# Port.net
KiCad netlist of a schematic drawn in Altium Designer
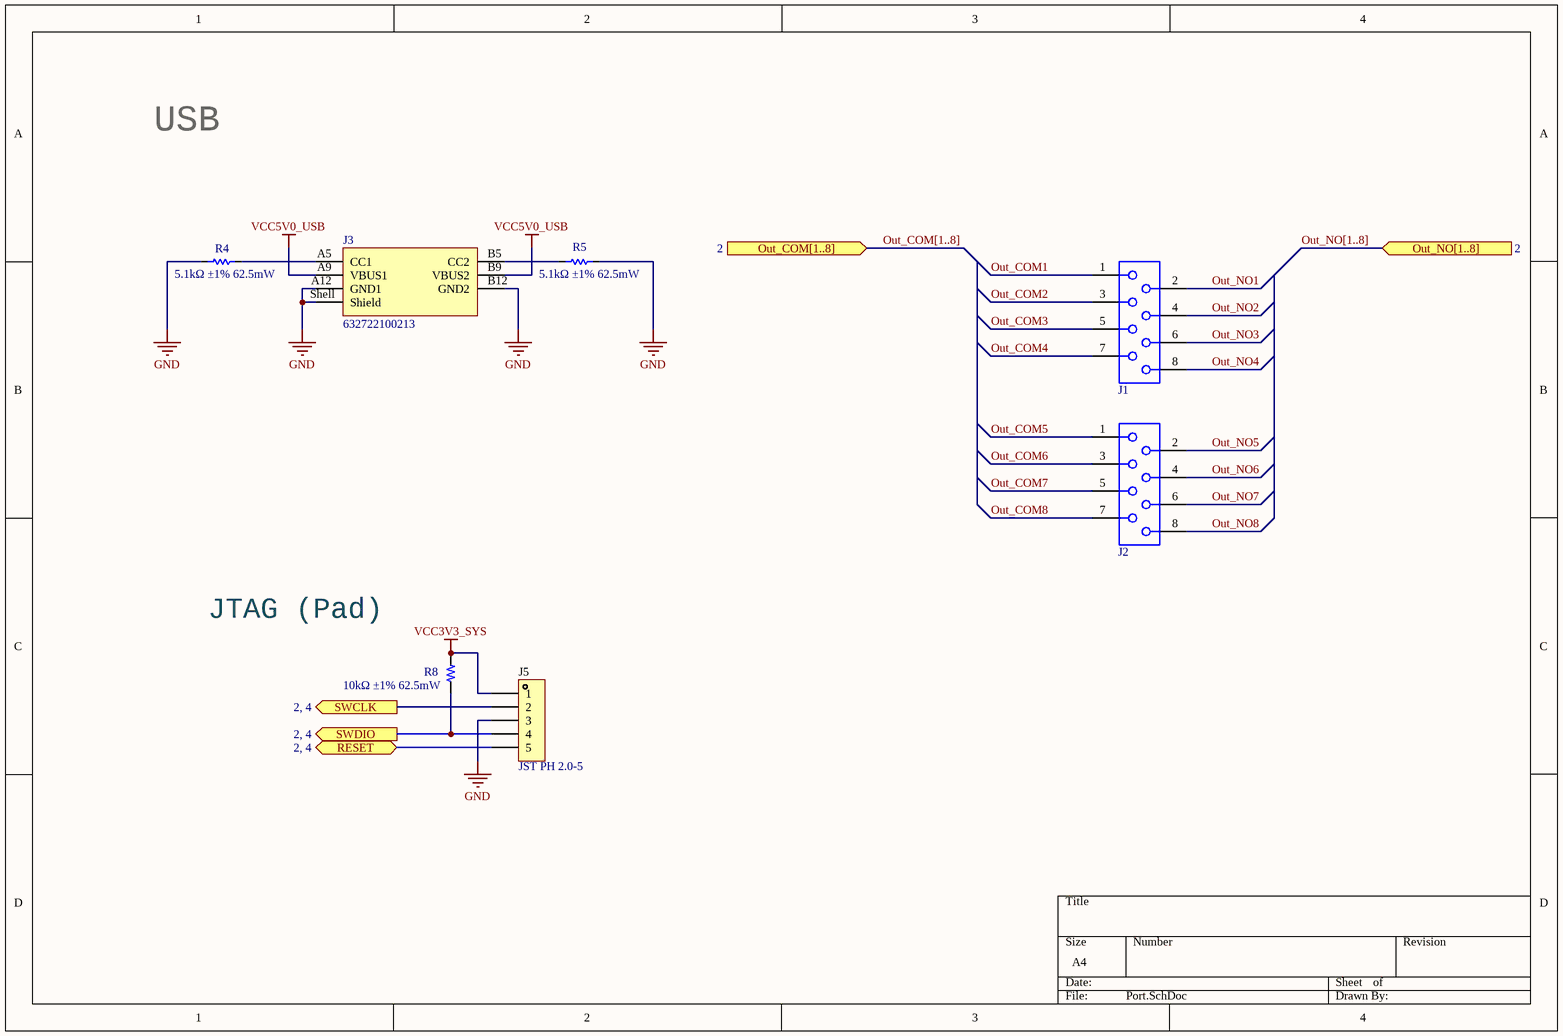
[diagram p0: Port.SchDoc]

(export (version "E")
  (design (tool "Eeschema 10.0.6"))
  (components
    (comp (ref "J1")
      (value "690367290876")
      (footprint "690367290876")
      (description "WR-MM Mini Module Connector, Female, SMT, with Latch & Polarization, Straight, pitch 2.54mm, 8p")
      (fields (field (name "MANUFACTURER") "Wurth Elektronik"))
      (libsource (lib "Altium_WR-MM (rev22a)") (part "690367290876"))
    )
    (comp (ref "J2")
      (value "690367290876")
      (footprint "690367290876")
      (description "WR-MM Mini Module Connector, Female, SMT, with Latch & Polarization, Straight, pitch 2.54mm, 8p")
      (fields (field (name "MANUFACTURER") "Wurth Elektronik"))
      (libsource (lib "Altium_WR-MM (rev22a)") (part "690367290876"))
    )
    (comp (ref "J3")
      (value "632722100213")
      (footprint "632722100213")
      (description "WR-COM USB Power Delivery Type C Receptacle Horizontal SMT")
      (fields (field (name "MANUFACTURER") "Wurth Elektronik"))
      (libsource (lib "Altium_WR-USB (rev24e)") (part "632722100213"))
    )
    (comp (ref "J5")
      (value "JST PH 2.0-5")
      (footprint "CONN-TH_B5B-PH-K-S-LF-SN")
      (description "B5B-PH-K-S")
      (fields
        (field (name "MANUFACTURER") "BOOMELE(博穆精密)")
        (field (name "MANUFACTURER PART") "GH1.25-5PLTPZ")
      )
      (libsource (lib "Connectivity_Plugs") (part "PH2.0-5P"))
    )
    (comp (ref "R4")
      (value "5.1kΩ ±1% 62.5mW")
      (footprint "R0402")
      (description "Resistor")
      (fields (field (name "PUBLISHER") "Altium Limited"))
      (libsource (lib "Component") (part "Res"))
    )
    (comp (ref "R5")
      (value "5.1kΩ ±1% 62.5mW")
      (footprint "R0402")
      (description "Resistor")
      (fields (field (name "PUBLISHER") "Altium Limited"))
      (libsource (lib "Component") (part "Res"))
    )
    (comp (ref "R8")
      (value "10kΩ ±1% 62.5mW")
      (footprint "R0402")
      (description "0402WGF1002TCE")
      (libsource (lib "Device") (part "R-0603"))
    )
  )
  (nets
    (net (code "1") (name "/Out_COM1") (class "Default")
      (node (ref "J1") (pin "1") (pinfunction "1_1") (pintype "passive"))
    )
    (net (code "2") (name "/Out_COM2") (class "Default")
      (node (ref "J1") (pin "3") (pinfunction "3_3") (pintype "passive"))
    )
    (net (code "3") (name "/Out_COM3") (class "Default")
      (node (ref "J1") (pin "5") (pinfunction "5_5") (pintype "passive"))
    )
    (net (code "4") (name "/Out_COM4") (class "Default")
      (node (ref "J1") (pin "7") (pinfunction "7_7") (pintype "passive"))
    )
    (net (code "5") (name "/Out_COM5") (class "Default")
      (node (ref "J2") (pin "1") (pinfunction "1_1") (pintype "passive"))
    )
    (net (code "6") (name "/Out_COM6") (class "Default")
      (node (ref "J2") (pin "3") (pinfunction "3_3") (pintype "passive"))
    )
    (net (code "7") (name "/Out_COM7") (class "Default")
      (node (ref "J2") (pin "5") (pinfunction "5_5") (pintype "passive"))
    )
    (net (code "8") (name "/Out_COM8") (class "Default")
      (node (ref "J2") (pin "7") (pinfunction "7_7") (pintype "passive"))
    )
    (net (code "10") (name "/Out_NO1") (class "Default")
      (node (ref "J1") (pin "2") (pinfunction "2_2") (pintype "passive"))
    )
    (net (code "11") (name "/Out_NO2") (class "Default")
      (node (ref "J1") (pin "4") (pinfunction "4_4") (pintype "passive"))
    )
    (net (code "12") (name "/Out_NO3") (class "Default")
      (node (ref "J1") (pin "6") (pinfunction "6_6") (pintype "passive"))
    )
    (net (code "13") (name "/Out_NO4") (class "Default")
      (node (ref "J1") (pin "8") (pinfunction "8_8") (pintype "passive"))
    )
    (net (code "14") (name "/Out_NO5") (class "Default")
      (node (ref "J2") (pin "2") (pinfunction "2_2") (pintype "passive"))
    )
    (net (code "15") (name "/Out_NO6") (class "Default")
      (node (ref "J2") (pin "4") (pinfunction "4_4") (pintype "passive"))
    )
    (net (code "16") (name "/Out_NO7") (class "Default")
      (node (ref "J2") (pin "6") (pinfunction "6_6") (pintype "passive"))
    )
    (net (code "17") (name "/Out_NO8") (class "Default")
      (node (ref "J2") (pin "8") (pinfunction "8_8") (pintype "passive"))
    )
    (net (code "19") (name "/RESET") (class "Default")
      (node (ref "J5") (pin "5") (pinfunction "5_5") (pintype "passive"))
    )
    (net (code "20") (name "/SWCLK") (class "Default")
      (node (ref "J5") (pin "2") (pinfunction "2_2") (pintype "passive"))
    )
    (net (code "21") (name "/SWDIO") (class "Default")
      (node (ref "J5") (pin "4") (pinfunction "4_4") (pintype "passive"))
      (node (ref "R8") (pin "1") (pinfunction "1_1") (pintype "passive"))
    )
    (net (code "22") (name "GND") (class "Default")
      (node (ref "J3") (pin "A12") (pinfunction "GND1_A12") (pintype "passive"))
      (node (ref "J3") (pin "B12") (pinfunction "GND2_B12") (pintype "passive"))
      (node (ref "J3") (pin "Shell") (pinfunction "Shield_Shell") (pintype "passive"))
      (node (ref "J5") (pin "3") (pinfunction "3_3") (pintype "passive"))
      (node (ref "R4") (pin "1") (pinfunction "1_1") (pintype "passive"))
      (node (ref "R5") (pin "2") (pinfunction "2_2") (pintype "passive"))
    )
    (net (code "23") (name "Net-(J3-CC1)") (class "Default")
      (node (ref "J3") (pin "A5") (pinfunction "CC1_A5") (pintype "passive"))
      (node (ref "R4") (pin "2") (pinfunction "2_2") (pintype "passive"))
    )
    (net (code "24") (name "Net-(J3-CC2)") (class "Default")
      (node (ref "J3") (pin "B5") (pinfunction "CC2_B5") (pintype "passive"))
      (node (ref "R5") (pin "1") (pinfunction "1_1") (pintype "passive"))
    )
    (net (code "25") (name "VCC3V3_SYS") (class "Default")
      (node (ref "J5") (pin "1") (pinfunction "1_1") (pintype "passive"))
      (node (ref "R8") (pin "2") (pinfunction "2_2") (pintype "passive"))
    )
    (net (code "26") (name "VCC5V0_USB") (class "Default")
      (node (ref "J3") (pin "A9") (pinfunction "VBUS1_A9") (pintype "passive"))
      (node (ref "J3") (pin "B9") (pinfunction "VBUS2_B9") (pintype "passive"))
    )
  )
)
